# touch_r_7.net
KiCad netlist of a schematic drawn in EAGLE
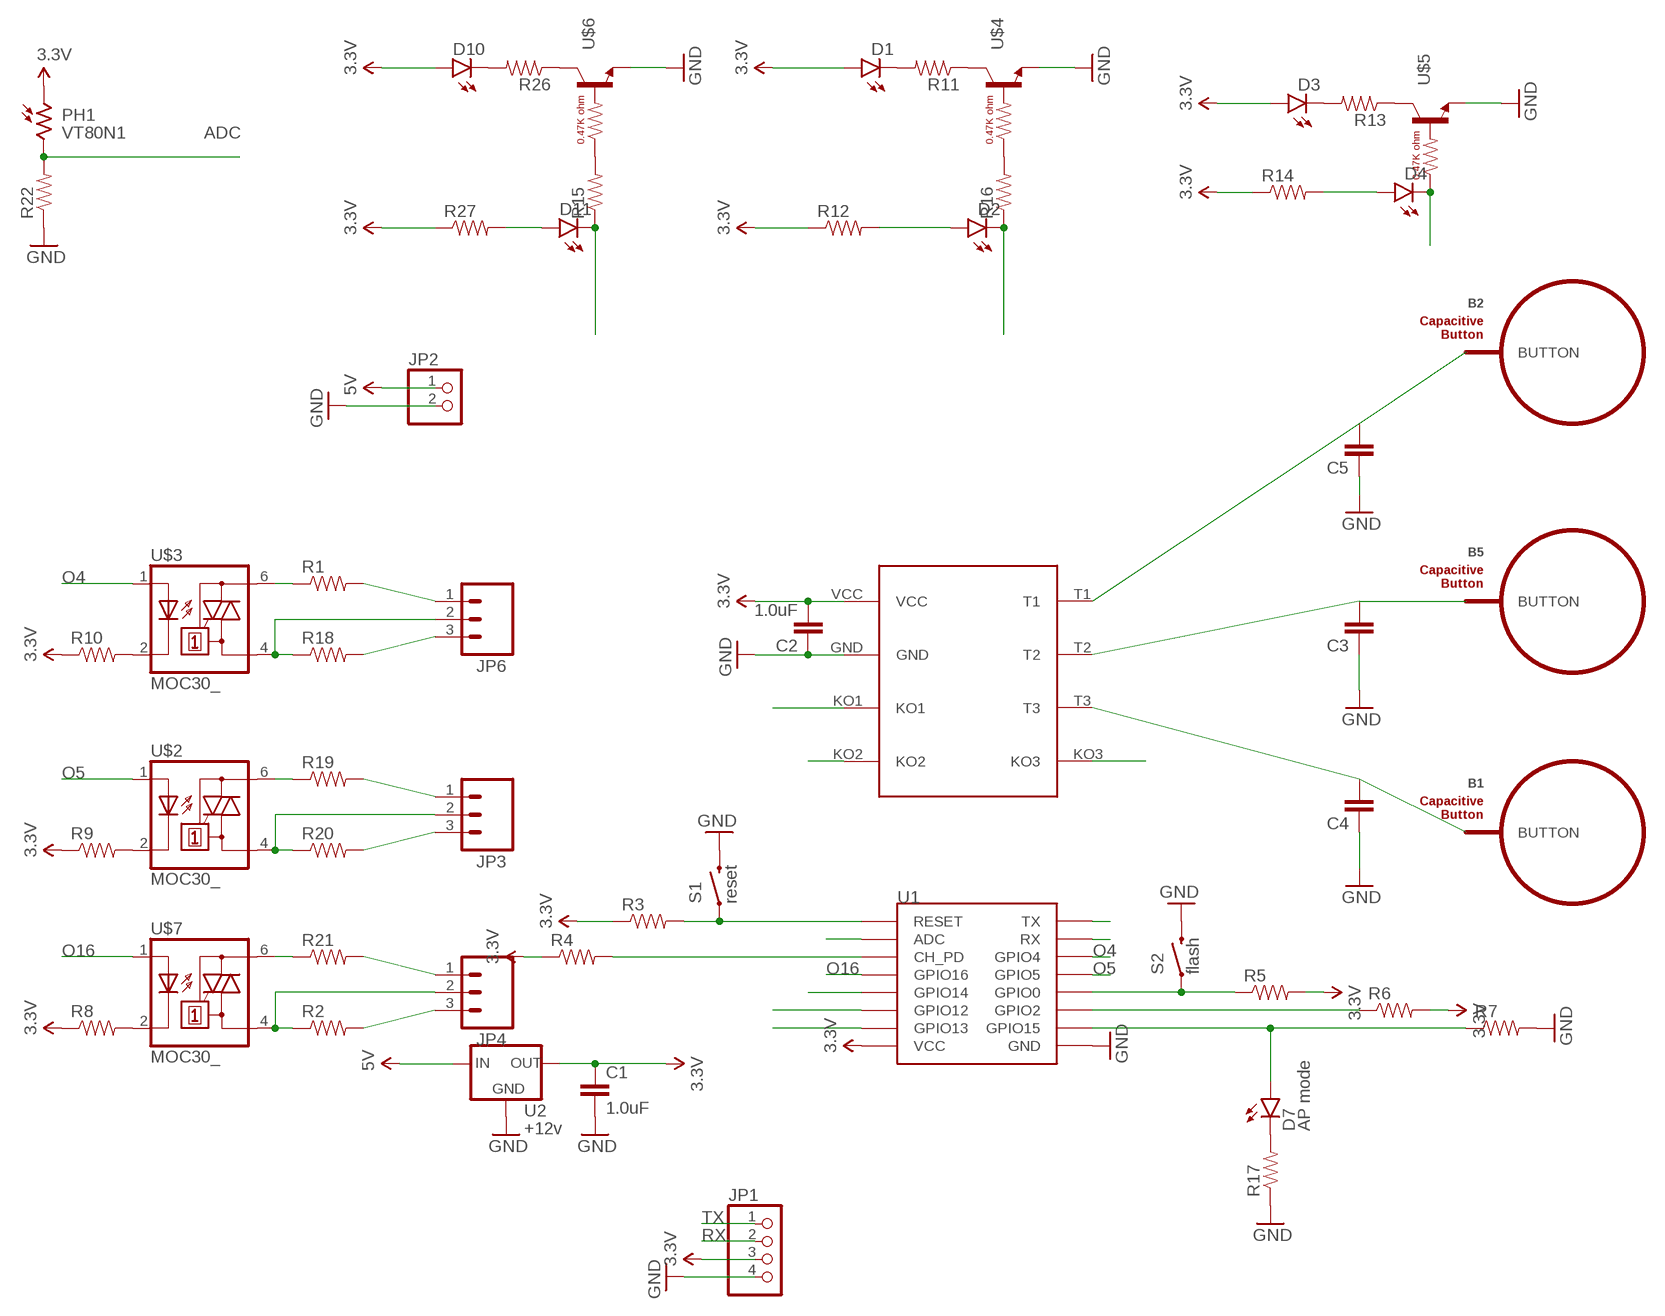
[diagram p0: schematic, sheet 1]

(export (version "E")
  (design (tool "Eeschema 10.0.6"))
  (components
    (comp (ref "B1")
      (value "BUTTON_PASSIVE12MM")
      (footprint "eagle-import:BUTTON_PASSIVE_12MM")
      (libsource (lib "eagle-import") (part "BUTTON_PASSIVE12MM"))
    )
    (comp (ref "B2")
      (value "BUTTON_PASSIVE12MM")
      (footprint "eagle-import:BUTTON_PASSIVE_12MM")
      (libsource (lib "eagle-import") (part "BUTTON_PASSIVE12MM"))
    )
    (comp (ref "B5")
      (value "BUTTON_PASSIVE12MM")
      (footprint "eagle-import:BUTTON_PASSIVE_12MM")
      (libsource (lib "eagle-import") (part "BUTTON_PASSIVE12MM"))
    )
    (comp (ref "C1")
      (value "1.0uF")
      (footprint "eagle-import:1206")
      (libsource (lib "eagle-import") (part "1.0UF50V10%(1206)"))
    )
    (comp (ref "C2")
      (value "1.0uF")
      (footprint "eagle-import:1206")
      (libsource (lib "eagle-import") (part "1.0UF50V10%(1206)"))
    )
    (comp (ref "C3")
      (value "1.0UF-25V-+80/-20(0805)\"")
      (footprint "eagle-import:0805-CAP")
      (libsource (lib "eagle-import") (part "1.0UF-25V-+80/-20(0805){dblquote}"))
    )
    (comp (ref "C4")
      (value "1.0UF-25V-+80/-20(0805)\"")
      (footprint "eagle-import:0805-CAP")
      (libsource (lib "eagle-import") (part "1.0UF-25V-+80/-20(0805){dblquote}"))
    )
    (comp (ref "C5")
      (value "1.0UF-25V-+80/-20(0805)\"")
      (footprint "eagle-import:0805-CAP")
      (libsource (lib "eagle-import") (part "1.0UF-25V-+80/-20(0805){dblquote}"))
    )
    (comp (ref "D1")
      (value "LED-GREENLILYPAD")
      (footprint "eagle-import:LED-1206")
      (libsource (lib "eagle-import") (part "LED-GREENLILYPAD"))
    )
    (comp (ref "D2")
      (value "LED-GREENLILYPAD")
      (footprint "eagle-import:LED-1206")
      (libsource (lib "eagle-import") (part "LED-GREENLILYPAD"))
    )
    (comp (ref "D3")
      (value "LED-GREENLILYPAD")
      (footprint "eagle-import:LED-1206")
      (libsource (lib "eagle-import") (part "LED-GREENLILYPAD"))
    )
    (comp (ref "D4")
      (value "LED-GREENLILYPAD")
      (footprint "eagle-import:LED-1206")
      (libsource (lib "eagle-import") (part "LED-GREENLILYPAD"))
    )
    (comp (ref "D7")
      (value "AP mode")
      (footprint "eagle-import:LED-1206")
      (libsource (lib "eagle-import") (part "LED-GREENLILYPAD"))
    )
    (comp (ref "D10")
      (value "LED-GREENLILYPAD")
      (footprint "eagle-import:LED-1206")
      (libsource (lib "eagle-import") (part "LED-GREENLILYPAD"))
    )
    (comp (ref "D11")
      (value "LED-GREENLILYPAD")
      (footprint "eagle-import:LED-1206")
      (libsource (lib "eagle-import") (part "LED-GREENLILYPAD"))
    )
    (comp (ref "JP1")
      (value "PINHD-1X4")
      (footprint "eagle-import:1X04")
      (libsource (lib "eagle-import") (part "PINHD-1X4"))
    )
    (comp (ref "JP2")
      (value "PINHD-1X2")
      (footprint "eagle-import:1X02")
      (libsource (lib "eagle-import") (part "PINHD-1X2"))
    )
    (comp (ref "JP3")
      (value "M03LONGPADS")
      (footprint "eagle-import:1X03_LONGPADS")
      (libsource (lib "eagle-import") (part "M03LONGPADS"))
    )
    (comp (ref "JP4")
      (value "M03LONGPADS")
      (footprint "eagle-import:1X03_LONGPADS")
      (libsource (lib "eagle-import") (part "M03LONGPADS"))
    )
    (comp (ref "JP6")
      (value "M03LONGPADS")
      (footprint "eagle-import:1X03_LONGPADS")
      (libsource (lib "eagle-import") (part "M03LONGPADS"))
    )
    (comp (ref "PH1")
      (value "VT80N1")
      (footprint "eagle-import:VT800")
      (libsource (lib "eagle-import") (part "VT80N1"))
    )
    (comp (ref "R1")
      (value "RESISTORPTH-1/2W")
      (footprint "eagle-import:AXIAL-0.5")
      (libsource (lib "eagle-import") (part "RESISTORPTH-1/2W"))
    )
    (comp (ref "R2")
      (value "RESISTORPTH-1/2W")
      (footprint "eagle-import:AXIAL-0.5")
      (libsource (lib "eagle-import") (part "RESISTORPTH-1/2W"))
    )
    (comp (ref "R3")
      (value "0.3OHM-1/8W-1%(0805)")
      (footprint "eagle-import:0805")
      (libsource (lib "eagle-import") (part "0.3OHM-1/8W-1%(0805)"))
    )
    (comp (ref "R4")
      (value "0.3OHM-1/8W-1%(0805)")
      (footprint "eagle-import:0805")
      (libsource (lib "eagle-import") (part "0.3OHM-1/8W-1%(0805)"))
    )
    (comp (ref "R5")
      (value "0.3OHM-1/8W-1%(0805)")
      (footprint "eagle-import:0805")
      (libsource (lib "eagle-import") (part "0.3OHM-1/8W-1%(0805)"))
    )
    (comp (ref "R6")
      (value "0.3OHM-1/8W-1%(0805)")
      (footprint "eagle-import:0805")
      (libsource (lib "eagle-import") (part "0.3OHM-1/8W-1%(0805)"))
    )
    (comp (ref "R7")
      (value "0.3OHM-1/8W-1%(0805)")
      (footprint "eagle-import:0805")
      (libsource (lib "eagle-import") (part "0.3OHM-1/8W-1%(0805)"))
    )
    (comp (ref "R8")
      (value "0.3OHM-1/8W-1%(0805)")
      (footprint "eagle-import:0805")
      (libsource (lib "eagle-import") (part "0.3OHM-1/8W-1%(0805)"))
    )
    (comp (ref "R9")
      (value "0.3OHM-1/8W-1%(0805)")
      (footprint "eagle-import:0805")
      (libsource (lib "eagle-import") (part "0.3OHM-1/8W-1%(0805)"))
    )
    (comp (ref "R10")
      (value "0.3OHM-1/8W-1%(0805)")
      (footprint "eagle-import:0805")
      (libsource (lib "eagle-import") (part "0.3OHM-1/8W-1%(0805)"))
    )
    (comp (ref "R11")
      (value "0.3OHM-1/8W-1%(0805)")
      (footprint "eagle-import:0805")
      (libsource (lib "eagle-import") (part "0.3OHM-1/8W-1%(0805)"))
    )
    (comp (ref "R12")
      (value "0.3OHM-1/8W-1%(0805)")
      (footprint "eagle-import:0805")
      (libsource (lib "eagle-import") (part "0.3OHM-1/8W-1%(0805)"))
    )
    (comp (ref "R13")
      (value "0.3OHM-1/8W-1%(0805)")
      (footprint "eagle-import:0805")
      (libsource (lib "eagle-import") (part "0.3OHM-1/8W-1%(0805)"))
    )
    (comp (ref "R14")
      (value "0.3OHM-1/8W-1%(0805)")
      (footprint "eagle-import:0805")
      (libsource (lib "eagle-import") (part "0.3OHM-1/8W-1%(0805)"))
    )
    (comp (ref "R15")
      (value "0.3OHM-1/8W-1%(0805)")
      (footprint "eagle-import:0805")
      (libsource (lib "eagle-import") (part "0.3OHM-1/8W-1%(0805)"))
    )
    (comp (ref "R16")
      (value "0.3OHM-1/8W-1%(0805)")
      (footprint "eagle-import:0805")
      (libsource (lib "eagle-import") (part "0.3OHM-1/8W-1%(0805)"))
    )
    (comp (ref "R17")
      (value "0.3OHM-1/8W-1%(0805)")
      (footprint "eagle-import:0805")
      (libsource (lib "eagle-import") (part "0.3OHM-1/8W-1%(0805)"))
    )
    (comp (ref "R18")
      (value "RESISTORPTH-1/2W")
      (footprint "eagle-import:AXIAL-0.5")
      (libsource (lib "eagle-import") (part "RESISTORPTH-1/2W"))
    )
    (comp (ref "R19")
      (value "RESISTORPTH-1/2W")
      (footprint "eagle-import:AXIAL-0.5")
      (libsource (lib "eagle-import") (part "RESISTORPTH-1/2W"))
    )
    (comp (ref "R20")
      (value "RESISTORPTH-1/2W")
      (footprint "eagle-import:AXIAL-0.5")
      (libsource (lib "eagle-import") (part "RESISTORPTH-1/2W"))
    )
    (comp (ref "R21")
      (value "RESISTORPTH-1/2W")
      (footprint "eagle-import:AXIAL-0.5")
      (libsource (lib "eagle-import") (part "RESISTORPTH-1/2W"))
    )
    (comp (ref "R22")
      (value "0.3OHM-1/8W-1%(0805)")
      (footprint "eagle-import:0805")
      (libsource (lib "eagle-import") (part "0.3OHM-1/8W-1%(0805)"))
    )
    (comp (ref "R26")
      (value "0.3OHM-1/8W-1%(0805)")
      (footprint "eagle-import:0805")
      (libsource (lib "eagle-import") (part "0.3OHM-1/8W-1%(0805)"))
    )
    (comp (ref "R27")
      (value "0.3OHM-1/8W-1%(0805)")
      (footprint "eagle-import:0805")
      (libsource (lib "eagle-import") (part "0.3OHM-1/8W-1%(0805)"))
    )
    (comp (ref "S1")
      (value "reset")
      (footprint "eagle-import:TACTILE-SWITCH-1101NE")
      (libsource (lib "eagle-import") (part "SWITCH-MOMENTARY-2SMD-1101NE"))
    )
    (comp (ref "S2")
      (value "flash")
      (footprint "eagle-import:TACTILE-SWITCH-1101NE")
      (libsource (lib "eagle-import") (part "SWITCH-MOMENTARY-2SMD-1101NE"))
    )
    (comp (ref "U$1")
      (value "BS813A")
      (footprint "eagle-import:BS813A_8PIN")
      (libsource (lib "eagle-import") (part "BS813A"))
    )
    (comp (ref "U$2")
      (value "MOC30_")
      (footprint "eagle-import:MOC_")
      (libsource (lib "eagle-import") (part "MOC30_"))
    )
    (comp (ref "U$3")
      (value "MOC30_")
      (footprint "eagle-import:MOC_")
      (libsource (lib "eagle-import") (part "MOC30_"))
    )
    (comp (ref "U$4")
      (value "TRANSISTOR-NPN-DDTD142TC")
      (footprint "eagle-import:SOT23-3")
      (libsource (lib "eagle-import") (part "TRANSISTOR-NPN-DDTD142TC"))
    )
    (comp (ref "U$5")
      (value "TRANSISTOR-NPN-DDTD142TC")
      (footprint "eagle-import:SOT23-3")
      (libsource (lib "eagle-import") (part "TRANSISTOR-NPN-DDTD142TC"))
    )
    (comp (ref "U$6")
      (value "TRANSISTOR-NPN-DDTD142TC")
      (footprint "eagle-import:SOT23-3")
      (libsource (lib "eagle-import") (part "TRANSISTOR-NPN-DDTD142TC"))
    )
    (comp (ref "U$7")
      (value "MOC30_")
      (footprint "eagle-import:MOC_")
      (libsource (lib "eagle-import") (part "MOC30_"))
    )
    (comp (ref "U1")
      (value "ESP12SMD")
      (footprint "eagle-import:ESP12-SMD")
      (libsource (lib "eagle-import") (part "ESP12SMD"))
    )
    (comp (ref "U2")
      (value "+12v")
      (footprint "eagle-import:TO-252")
      (libsource (lib "eagle-import") (part "V_REG_78XX7812"))
    )
  )
  (nets
    (net (code "1") (name "/12") (class "Default")
      (node (ref "U$1") (pin "KO2") (pinfunction "KO2_KO2") (pintype "bidirectional"))
      (node (ref "U1") (pin "GPIO12") (pinfunction "GPIO12_GPIO12") (pintype "bidirectional"))
    )
    (net (code "2") (name "/13") (class "Default")
      (node (ref "U$1") (pin "KO1") (pinfunction "KO1_KO1") (pintype "bidirectional"))
      (node (ref "U1") (pin "GPIO13") (pinfunction "GPIO13_GPIO13") (pintype "bidirectional"))
    )
    (net (code "3") (name "/14") (class "Default")
      (node (ref "U$1") (pin "KO3") (pinfunction "KO3_KO3") (pintype "bidirectional"))
      (node (ref "U1") (pin "GPIO14") (pinfunction "GPIO14_GPIO14") (pintype "bidirectional"))
    )
    (net (code "4") (name "/ADC") (class "Default")
      (node (ref "PH1") (pin "2") (pinfunction "2_2") (pintype "passive"))
      (node (ref "R22") (pin "2") (pinfunction "2_2") (pintype "passive"))
      (node (ref "U1") (pin "ADC") (pinfunction "ADC_ADC") (pintype "bidirectional"))
    )
    (net (code "5") (name "/O4") (class "Default")
      (node (ref "D11") (pin "C") (pinfunction "C_C") (pintype "passive"))
      (node (ref "R15") (pin "1") (pinfunction "1_1") (pintype "passive"))
      (node (ref "U$3") (pin "1") (pinfunction "1_1") (pintype "passive"))
      (node (ref "U1") (pin "GPIO4") (pinfunction "GPIO4_GPIO4") (pintype "bidirectional"))
    )
    (net (code "6") (name "/O5") (class "Default")
      (node (ref "D2") (pin "C") (pinfunction "C_C") (pintype "passive"))
      (node (ref "R16") (pin "1") (pinfunction "1_1") (pintype "passive"))
      (node (ref "U$2") (pin "1") (pinfunction "1_1") (pintype "passive"))
      (node (ref "U1") (pin "GPIO5") (pinfunction "GPIO5_GPIO5") (pintype "bidirectional"))
    )
    (net (code "7") (name "/O16") (class "Default")
      (node (ref "D4") (pin "C") (pinfunction "C_C") (pintype "passive"))
      (node (ref "U$5") (pin "1") (pinfunction "B_1") (pintype "passive"))
      (node (ref "U$7") (pin "1") (pinfunction "1_1") (pintype "passive"))
      (node (ref "U1") (pin "GPIO16") (pinfunction "GPIO16_GPIO16") (pintype "bidirectional"))
    )
    (net (code "8") (name "/RX") (class "Default")
      (node (ref "JP1") (pin "2") (pinfunction "2_2") (pintype "passive"))
      (node (ref "U1") (pin "RXD0") (pinfunction "RX_RXD0") (pintype "bidirectional"))
    )
    (net (code "9") (name "/TX") (class "Default")
      (node (ref "JP1") (pin "1") (pinfunction "1_1") (pintype "passive"))
      (node (ref "U1") (pin "TXD0") (pinfunction "TX_TXD0") (pintype "bidirectional"))
    )
    (net (code "10") (name "3.3V") (class "Default")
      (node (ref "C1") (pin "1") (pinfunction "1_1") (pintype "passive"))
      (node (ref "C2") (pin "2") (pinfunction "2_2") (pintype "passive"))
      (node (ref "D1") (pin "A") (pinfunction "A_A") (pintype "passive"))
      (node (ref "D10") (pin "A") (pinfunction "A_A") (pintype "passive"))
      (node (ref "D3") (pin "A") (pinfunction "A_A") (pintype "passive"))
      (node (ref "JP1") (pin "3") (pinfunction "3_3") (pintype "passive"))
      (node (ref "PH1") (pin "1") (pinfunction "1_1") (pintype "passive"))
      (node (ref "R10") (pin "1") (pinfunction "1_1") (pintype "passive"))
      (node (ref "R12") (pin "1") (pinfunction "1_1") (pintype "passive"))
      (node (ref "R14") (pin "1") (pinfunction "1_1") (pintype "passive"))
      (node (ref "R27") (pin "1") (pinfunction "1_1") (pintype "passive"))
      (node (ref "R3") (pin "1") (pinfunction "1_1") (pintype "passive"))
      (node (ref "R4") (pin "1") (pinfunction "1_1") (pintype "passive"))
      (node (ref "R5") (pin "2") (pinfunction "2_2") (pintype "passive"))
      (node (ref "R6") (pin "2") (pinfunction "2_2") (pintype "passive"))
      (node (ref "R8") (pin "1") (pinfunction "1_1") (pintype "passive"))
      (node (ref "R9") (pin "1") (pinfunction "1_1") (pintype "passive"))
      (node (ref "U$1") (pin "VCC") (pinfunction "VCC_VCC") (pintype "bidirectional"))
      (node (ref "U1") (pin "VCC") (pinfunction "VCC_VCC") (pintype "bidirectional"))
      (node (ref "U2") (pin "2") (pinfunction "OUT_2") (pintype "passive"))
    )
    (net (code "11") (name "5V") (class "Default")
      (node (ref "JP2") (pin "1") (pinfunction "1_1") (pintype "passive"))
      (node (ref "U2") (pin "1") (pinfunction "IN_1") (pintype "input"))
    )
    (net (code "12") (name "GND") (class "Default")
      (node (ref "C1") (pin "2") (pinfunction "2_2") (pintype "passive"))
      (node (ref "C2") (pin "1") (pinfunction "1_1") (pintype "passive"))
      (node (ref "C3") (pin "1") (pinfunction "1_1") (pintype "passive"))
      (node (ref "C4") (pin "1") (pinfunction "1_1") (pintype "passive"))
      (node (ref "C5") (pin "1") (pinfunction "1_1") (pintype "passive"))
      (node (ref "JP1") (pin "4") (pinfunction "4_4") (pintype "passive"))
      (node (ref "JP2") (pin "2") (pinfunction "2_2") (pintype "passive"))
      (node (ref "R17") (pin "1") (pinfunction "1_1") (pintype "passive"))
      (node (ref "R22") (pin "1") (pinfunction "1_1") (pintype "passive"))
      (node (ref "R7") (pin "2") (pinfunction "2_2") (pintype "passive"))
      (node (ref "S1") (pin "2") (pinfunction "2_2") (pintype "passive"))
      (node (ref "S2") (pin "2") (pinfunction "2_2") (pintype "passive"))
      (node (ref "U$1") (pin "GND") (pinfunction "GND_GND") (pintype "bidirectional"))
      (node (ref "U$4") (pin "2") (pinfunction "E_2") (pintype "passive"))
      (node (ref "U$5") (pin "2") (pinfunction "E_2") (pintype "passive"))
      (node (ref "U$6") (pin "2") (pinfunction "E_2") (pintype "passive"))
      (node (ref "U1") (pin "GND") (pinfunction "GND_GND") (pintype "bidirectional"))
      (node (ref "U2") (pin "3") (pinfunction "GND_3") (pintype "input"))
    )
    (net (code "13") (name "Net-(B1-PadBUTTON)") (class "Default")
      (node (ref "B1") (pin "BUTTON") (pinfunction "BUTTON_BUTTON") (pintype "passive"))
      (node (ref "C4") (pin "2") (pinfunction "2_2") (pintype "passive"))
      (node (ref "U$1") (pin "T3") (pinfunction "T3_T3") (pintype "bidirectional"))
    )
    (net (code "14") (name "Net-(B2-PadBUTTON)") (class "Default")
      (node (ref "B2") (pin "BUTTON") (pinfunction "BUTTON_BUTTON") (pintype "passive"))
      (node (ref "C5") (pin "2") (pinfunction "2_2") (pintype "passive"))
      (node (ref "U$1") (pin "T1") (pinfunction "T1_T1") (pintype "bidirectional"))
    )
    (net (code "15") (name "Net-(B5-PadBUTTON)") (class "Default")
      (node (ref "B5") (pin "BUTTON") (pinfunction "BUTTON_BUTTON") (pintype "passive"))
      (node (ref "C3") (pin "2") (pinfunction "2_2") (pintype "passive"))
      (node (ref "U$1") (pin "T2") (pinfunction "T2_T2") (pintype "bidirectional"))
    )
    (net (code "16") (name "Net-(D1-PadC)") (class "Default")
      (node (ref "D1") (pin "C") (pinfunction "C_C") (pintype "passive"))
      (node (ref "R11") (pin "2") (pinfunction "2_2") (pintype "passive"))
    )
    (net (code "17") (name "Net-(D2-PadA)") (class "Default")
      (node (ref "D2") (pin "A") (pinfunction "A_A") (pintype "passive"))
      (node (ref "R12") (pin "2") (pinfunction "2_2") (pintype "passive"))
    )
    (net (code "18") (name "Net-(D3-PadC)") (class "Default")
      (node (ref "D3") (pin "C") (pinfunction "C_C") (pintype "passive"))
      (node (ref "R13") (pin "2") (pinfunction "2_2") (pintype "passive"))
    )
    (net (code "19") (name "Net-(D4-PadA)") (class "Default")
      (node (ref "D4") (pin "A") (pinfunction "A_A") (pintype "passive"))
      (node (ref "R14") (pin "2") (pinfunction "2_2") (pintype "passive"))
    )
    (net (code "20") (name "Net-(D7-PadA)") (class "Default")
      (node (ref "D7") (pin "A") (pinfunction "A_A") (pintype "passive"))
      (node (ref "R7") (pin "1") (pinfunction "1_1") (pintype "passive"))
      (node (ref "U1") (pin "GPIO15") (pinfunction "GPIO15_GPIO15") (pintype "bidirectional"))
    )
    (net (code "21") (name "Net-(D7-PadC)") (class "Default")
      (node (ref "D7") (pin "C") (pinfunction "C_C") (pintype "passive"))
      (node (ref "R17") (pin "2") (pinfunction "2_2") (pintype "passive"))
    )
    (net (code "22") (name "Net-(D10-PadC)") (class "Default")
      (node (ref "D10") (pin "C") (pinfunction "C_C") (pintype "passive"))
      (node (ref "R26") (pin "2") (pinfunction "2_2") (pintype "passive"))
    )
    (net (code "23") (name "Net-(D11-PadA)") (class "Default")
      (node (ref "D11") (pin "A") (pinfunction "A_A") (pintype "passive"))
      (node (ref "R27") (pin "2") (pinfunction "2_2") (pintype "passive"))
    )
    (net (code "24") (name "Net-(R1-1)") (class "Default")
      (node (ref "R1") (pin "P$1") (pinfunction "1_P$1") (pintype "passive"))
      (node (ref "U$3") (pin "6") (pinfunction "6_6") (pintype "passive"))
    )
    (net (code "25") (name "Net-(R1-2)") (class "Default")
      (node (ref "JP6") (pin "1") (pinfunction "1_1") (pintype "passive"))
      (node (ref "R1") (pin "P$2") (pinfunction "2_P$2") (pintype "passive"))
    )
    (net (code "26") (name "Net-(R2-1)") (class "Default")
      (node (ref "JP4") (pin "2") (pinfunction "2_2") (pintype "passive"))
      (node (ref "R2") (pin "P$1") (pinfunction "1_P$1") (pintype "passive"))
      (node (ref "U$7") (pin "4") (pinfunction "4_4") (pintype "passive"))
    )
    (net (code "27") (name "Net-(R2-2)") (class "Default")
      (node (ref "JP4") (pin "3") (pinfunction "3_3") (pintype "passive"))
      (node (ref "R2") (pin "P$2") (pinfunction "2_P$2") (pintype "passive"))
    )
    (net (code "28") (name "Net-(R3-Pad2)") (class "Default")
      (node (ref "R3") (pin "2") (pinfunction "2_2") (pintype "passive"))
      (node (ref "S1") (pin "1") (pinfunction "1_1") (pintype "passive"))
      (node (ref "U1") (pin "RESET") (pinfunction "RESET_RESET") (pintype "bidirectional"))
    )
    (net (code "29") (name "Net-(R4-Pad2)") (class "Default")
      (node (ref "R4") (pin "2") (pinfunction "2_2") (pintype "passive"))
      (node (ref "U1") (pin "CH_PD") (pinfunction "CH_PD_CH_PD") (pintype "bidirectional"))
    )
    (net (code "30") (name "Net-(R5-Pad1)") (class "Default")
      (node (ref "R5") (pin "1") (pinfunction "1_1") (pintype "passive"))
      (node (ref "S2") (pin "1") (pinfunction "1_1") (pintype "passive"))
      (node (ref "U1") (pin "GPIO0") (pinfunction "GPIO0_GPIO0") (pintype "bidirectional"))
    )
    (net (code "31") (name "Net-(R6-Pad1)") (class "Default")
      (node (ref "R6") (pin "1") (pinfunction "1_1") (pintype "passive"))
      (node (ref "U1") (pin "GPIO2") (pinfunction "GPIO2_GPIO2") (pintype "bidirectional"))
    )
    (net (code "32") (name "Net-(R8-Pad2)") (class "Default")
      (node (ref "R8") (pin "2") (pinfunction "2_2") (pintype "passive"))
      (node (ref "U$7") (pin "2") (pinfunction "2_2") (pintype "passive"))
    )
    (net (code "33") (name "Net-(R9-Pad2)") (class "Default")
      (node (ref "R9") (pin "2") (pinfunction "2_2") (pintype "passive"))
      (node (ref "U$2") (pin "2") (pinfunction "2_2") (pintype "passive"))
    )
    (net (code "34") (name "Net-(R10-Pad2)") (class "Default")
      (node (ref "R10") (pin "2") (pinfunction "2_2") (pintype "passive"))
      (node (ref "U$3") (pin "2") (pinfunction "2_2") (pintype "passive"))
    )
    (net (code "35") (name "Net-(R18-1)") (class "Default")
      (node (ref "JP6") (pin "2") (pinfunction "2_2") (pintype "passive"))
      (node (ref "R18") (pin "P$1") (pinfunction "1_P$1") (pintype "passive"))
      (node (ref "U$3") (pin "4") (pinfunction "4_4") (pintype "passive"))
    )
    (net (code "36") (name "Net-(R18-2)") (class "Default")
      (node (ref "JP6") (pin "3") (pinfunction "3_3") (pintype "passive"))
      (node (ref "R18") (pin "P$2") (pinfunction "2_P$2") (pintype "passive"))
    )
    (net (code "37") (name "Net-(R19-1)") (class "Default")
      (node (ref "R19") (pin "P$1") (pinfunction "1_P$1") (pintype "passive"))
      (node (ref "U$2") (pin "6") (pinfunction "6_6") (pintype "passive"))
    )
    (net (code "38") (name "Net-(R19-2)") (class "Default")
      (node (ref "JP3") (pin "1") (pinfunction "1_1") (pintype "passive"))
      (node (ref "R19") (pin "P$2") (pinfunction "2_P$2") (pintype "passive"))
    )
    (net (code "39") (name "Net-(R20-1)") (class "Default")
      (node (ref "JP3") (pin "2") (pinfunction "2_2") (pintype "passive"))
      (node (ref "R20") (pin "P$1") (pinfunction "1_P$1") (pintype "passive"))
      (node (ref "U$2") (pin "4") (pinfunction "4_4") (pintype "passive"))
    )
    (net (code "40") (name "Net-(R20-2)") (class "Default")
      (node (ref "JP3") (pin "3") (pinfunction "3_3") (pintype "passive"))
      (node (ref "R20") (pin "P$2") (pinfunction "2_P$2") (pintype "passive"))
    )
    (net (code "41") (name "Net-(R21-1)") (class "Default")
      (node (ref "R21") (pin "P$1") (pinfunction "1_P$1") (pintype "passive"))
      (node (ref "U$7") (pin "6") (pinfunction "6_6") (pintype "passive"))
    )
    (net (code "42") (name "Net-(R21-2)") (class "Default")
      (node (ref "JP4") (pin "1") (pinfunction "1_1") (pintype "passive"))
      (node (ref "R21") (pin "P$2") (pinfunction "2_P$2") (pintype "passive"))
    )
    (net (code "43") (name "Net-(U$4-B)") (class "Default")
      (node (ref "R16") (pin "2") (pinfunction "2_2") (pintype "passive"))
      (node (ref "U$4") (pin "1") (pinfunction "B_1") (pintype "passive"))
    )
    (net (code "44") (name "Net-(U$4-C)") (class "Default")
      (node (ref "R11") (pin "1") (pinfunction "1_1") (pintype "passive"))
      (node (ref "U$4") (pin "3") (pinfunction "C_3") (pintype "passive"))
    )
    (net (code "45") (name "Net-(U$5-C)") (class "Default")
      (node (ref "R13") (pin "1") (pinfunction "1_1") (pintype "passive"))
      (node (ref "U$5") (pin "3") (pinfunction "C_3") (pintype "passive"))
    )
    (net (code "46") (name "Net-(U$6-B)") (class "Default")
      (node (ref "R15") (pin "2") (pinfunction "2_2") (pintype "passive"))
      (node (ref "U$6") (pin "1") (pinfunction "B_1") (pintype "passive"))
    )
    (net (code "47") (name "Net-(U$6-C)") (class "Default")
      (node (ref "R26") (pin "1") (pinfunction "1_1") (pintype "passive"))
      (node (ref "U$6") (pin "3") (pinfunction "C_3") (pintype "passive"))
    )
  )
)
